# telekarte.net
KiCad netlist of a schematic drawn in EAGLE
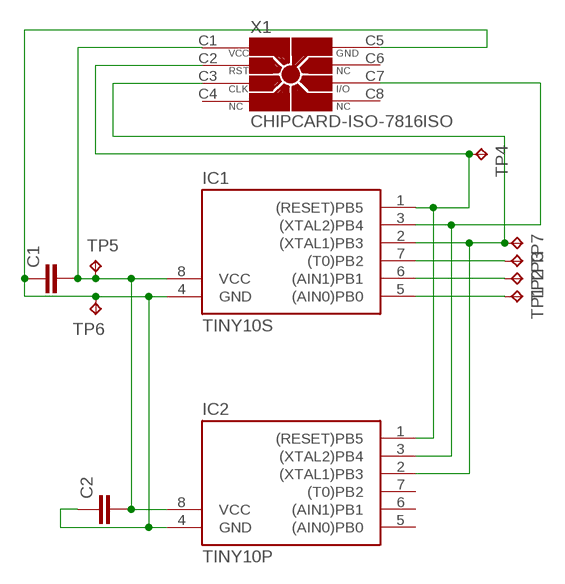
[diagram p0: schematic, sheet 1]

(export (version "E")
  (design (tool "Eeschema 10.0.6"))
  (components
    (comp (ref "C1")
      (value "C-EUC0805")
      (footprint "eagle-import:C0805")
      (libsource (lib "eagle-import") (part "C-EUC0805"))
    )
    (comp (ref "C2")
      (value "C-EUC0805")
      (footprint "eagle-import:C0805")
      (libsource (lib "eagle-import") (part "C-EUC0805"))
    )
    (comp (ref "IC1")
      (value "TINY10S")
      (footprint "eagle-import:SO08")
      (libsource (lib "eagle-import") (part "TINY10S"))
    )
    (comp (ref "IC2")
      (value "TINY10P")
      (footprint "eagle-import:DIL08")
      (libsource (lib "eagle-import") (part "TINY10P"))
    )
    (comp (ref "TP1")
      (value "TPTP10SQ")
      (footprint "eagle-import:TP10SQ")
      (libsource (lib "eagle-import") (part "TPTP10SQ"))
    )
    (comp (ref "TP2")
      (value "TPTP10SQ")
      (footprint "eagle-import:TP10SQ")
      (libsource (lib "eagle-import") (part "TPTP10SQ"))
    )
    (comp (ref "TP3")
      (value "TPTP10SQ")
      (footprint "eagle-import:TP10SQ")
      (libsource (lib "eagle-import") (part "TPTP10SQ"))
    )
    (comp (ref "TP4")
      (value "TPTP10SQ")
      (footprint "eagle-import:TP10SQ")
      (libsource (lib "eagle-import") (part "TPTP10SQ"))
    )
    (comp (ref "TP5")
      (value "TPTP10SQ")
      (footprint "eagle-import:TP10SQ")
      (libsource (lib "eagle-import") (part "TPTP10SQ"))
    )
    (comp (ref "TP6")
      (value "TPTP10SQ")
      (footprint "eagle-import:TP10SQ")
      (libsource (lib "eagle-import") (part "TPTP10SQ"))
    )
    (comp (ref "TP7")
      (value "TPTP10SQ")
      (footprint "eagle-import:TP10SQ")
      (libsource (lib "eagle-import") (part "TPTP10SQ"))
    )
    (comp (ref "X1")
      (value "CHIPCARD-ISO-7816ISO")
      (footprint "eagle-import:ISO-7816")
      (libsource (lib "eagle-import") (part "CHIPCARD-ISO-7816ISO"))
    )
  )
  (nets
    (net (code "1") (name "Net-(IC1-(AIN0)PB0)") (class "Default")
      (node (ref "IC1") (pin "5") (pinfunction "(AIN0)PB0_5") (pintype "bidirectional"))
      (node (ref "TP1") (pin "TP") (pinfunction "TP_TP") (pintype "input"))
    )
    (net (code "2") (name "Net-(IC1-(AIN1)PB1)") (class "Default")
      (node (ref "IC1") (pin "6") (pinfunction "(AIN1)PB1_6") (pintype "bidirectional"))
      (node (ref "TP2") (pin "TP") (pinfunction "TP_TP") (pintype "input"))
    )
    (net (code "3") (name "Net-(IC1-(RESET)PB5)") (class "Default")
      (node (ref "IC1") (pin "1") (pinfunction "(RESET)PB5_1") (pintype "bidirectional"))
      (node (ref "IC2") (pin "1") (pinfunction "(RESET)PB5_1") (pintype "bidirectional"))
      (node (ref "TP4") (pin "TP") (pinfunction "TP_TP") (pintype "input"))
      (node (ref "X1") (pin "C2") (pinfunction "RST_C2") (pintype "passive"))
    )
    (net (code "4") (name "Net-(IC1-(T0)PB2)") (class "Default")
      (node (ref "IC1") (pin "7") (pinfunction "(T0)PB2_7") (pintype "bidirectional"))
      (node (ref "TP3") (pin "TP") (pinfunction "TP_TP") (pintype "input"))
    )
    (net (code "5") (name "Net-(IC1-(XTAL1)PB3)") (class "Default")
      (node (ref "IC1") (pin "2") (pinfunction "(XTAL1)PB3_2") (pintype "bidirectional"))
      (node (ref "IC2") (pin "2") (pinfunction "(XTAL1)PB3_2") (pintype "bidirectional"))
      (node (ref "TP7") (pin "TP") (pinfunction "TP_TP") (pintype "input"))
      (node (ref "X1") (pin "C3") (pinfunction "CLK_C3") (pintype "passive"))
    )
    (net (code "6") (name "Net-(IC1-(XTAL2)PB4)") (class "Default")
      (node (ref "IC1") (pin "3") (pinfunction "(XTAL2)PB4_3") (pintype "bidirectional"))
      (node (ref "IC2") (pin "3") (pinfunction "(XTAL2)PB4_3") (pintype "bidirectional"))
      (node (ref "X1") (pin "C7") (pinfunction "I/O_C7") (pintype "passive"))
    )
    (net (code "7") (name "Net-(IC1-GND)") (class "Default")
      (node (ref "C1") (pin "1") (pinfunction "1_1") (pintype "passive"))
      (node (ref "C2") (pin "1") (pinfunction "1_1") (pintype "passive"))
      (node (ref "IC1") (pin "4") (pinfunction "GND_4") (pintype "power_in"))
      (node (ref "IC2") (pin "4") (pinfunction "GND_4") (pintype "power_in"))
      (node (ref "TP6") (pin "TP") (pinfunction "TP_TP") (pintype "input"))
      (node (ref "X1") (pin "C5") (pinfunction "GND_C5") (pintype "passive"))
    )
    (net (code "8") (name "Net-(IC1-VCC)") (class "Default")
      (node (ref "C1") (pin "2") (pinfunction "2_2") (pintype "passive"))
      (node (ref "C2") (pin "2") (pinfunction "2_2") (pintype "passive"))
      (node (ref "IC1") (pin "8") (pinfunction "VCC_8") (pintype "power_in"))
      (node (ref "IC2") (pin "8") (pinfunction "VCC_8") (pintype "power_in"))
      (node (ref "TP5") (pin "TP") (pinfunction "TP_TP") (pintype "input"))
      (node (ref "X1") (pin "C1") (pinfunction "VCC_C1") (pintype "passive"))
    )
    (net (code "9") (name "unconnected-(IC2-(AIN0)PB0-Pad5)") (class "Default")
      (node (ref "IC2") (pin "5") (pinfunction "(AIN0)PB0_5") (pintype "bidirectional"))
    )
    (net (code "10") (name "unconnected-(IC2-(AIN1)PB1-Pad6)") (class "Default")
      (node (ref "IC2") (pin "6") (pinfunction "(AIN1)PB1_6") (pintype "bidirectional"))
    )
    (net (code "11") (name "unconnected-(IC2-(T0)PB2-Pad7)") (class "Default")
      (node (ref "IC2") (pin "7") (pinfunction "(T0)PB2_7") (pintype "bidirectional"))
    )
    (net (code "12") (name "unconnected-(X1-NC-PadC4)") (class "Default")
      (node (ref "X1") (pin "C4") (pinfunction "NC_C4") (pintype "passive"))
    )
    (net (code "13") (name "unconnected-(X1-NC-PadC6)") (class "Default")
      (node (ref "X1") (pin "C6") (pinfunction "NC_C6") (pintype "passive"))
    )
    (net (code "14") (name "unconnected-(X1-NC-PadC8)") (class "Default")
      (node (ref "X1") (pin "C8") (pinfunction "NC_C8") (pintype "passive"))
    )
  )
)
